# 1_P1.net
KiCad netlist of a schematic drawn in Altium Designer
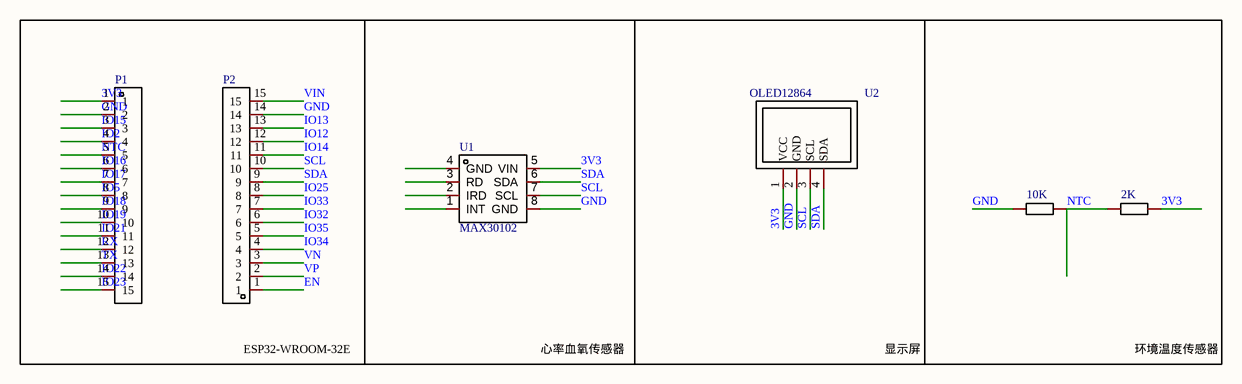
[diagram p0: 1_P1.schdoc]

(export (version "E")
  (design (tool "Eeschema 10.0.6"))
  (components
    (comp (ref "2K") (value "10K插件电阻") (libsource (lib "altium-import") (part "root_0_10K插件电阻_")))
    (comp (ref "10K")
      (value "10K")
      (fields (field (name "MANUFACTURER") "UniOhm") (field (name "MANUFACTURER PART") "0603WAF1002T5E"))
      (libsource (lib "altium-import") (part "root_0_10K_"))
    )
    (comp (ref "P1") (value "排针15pin") (libsource (lib "altium-import") (part "root_0_排针15pin_")))
    (comp (ref "P2") (value "排针15pin") (libsource (lib "altium-import") (part "root_2_排针15pin_")))
    (comp (ref "U1") (value "MAX30102") (libsource (lib "altium-import") (part "root_0_MAX30102_")))
    (comp (ref "U2") (value "OLED12864") (libsource (lib "altium-import") (part "root_0_OLED12864_")))
  )
  (nets
    (net (code "1") (name "/3V3") (class "Default")
      (node (ref "2K") (pin "2") (pinfunction "2_2") (pintype "passive"))
      (node (ref "P1") (pin "1") (pinfunction "1_1") (pintype "passive"))
      (node (ref "U1") (pin "5") (pinfunction "VIN_5") (pintype "passive"))
      (node (ref "U2") (pin "1") (pinfunction "VCC_1") (pintype "passive"))
    )
    (net (code "2") (name "/EN") (class "Default")
      (node (ref "P2") (pin "1") (pinfunction "1_1") (pintype "passive"))
    )
    (net (code "3") (name "/GND") (class "Default")
      (node (ref "10K") (pin "1") (pinfunction "1_1") (pintype "passive"))
      (node (ref "P1") (pin "2") (pinfunction "2_2") (pintype "passive"))
      (node (ref "P2") (pin "14") (pinfunction "14_14") (pintype "passive"))
      (node (ref "U1") (pin "8") (pinfunction "GND_8") (pintype "passive"))
      (node (ref "U2") (pin "2") (pinfunction "GND_2") (pintype "passive"))
    )
    (net (code "4") (name "/IO2") (class "Default")
      (node (ref "P1") (pin "4") (pinfunction "4_4") (pintype "passive"))
    )
    (net (code "5") (name "/IO5") (class "Default")
      (node (ref "P1") (pin "8") (pinfunction "8_8") (pintype "passive"))
    )
    (net (code "6") (name "/IO12") (class "Default")
      (node (ref "P2") (pin "12") (pinfunction "12_12") (pintype "passive"))
    )
    (net (code "7") (name "/IO13") (class "Default")
      (node (ref "P2") (pin "13") (pinfunction "13_13") (pintype "passive"))
    )
    (net (code "8") (name "/IO14") (class "Default")
      (node (ref "P2") (pin "11") (pinfunction "11_11") (pintype "passive"))
    )
    (net (code "9") (name "/IO15") (class "Default")
      (node (ref "P1") (pin "3") (pinfunction "3_3") (pintype "passive"))
    )
    (net (code "10") (name "/IO16") (class "Default")
      (node (ref "P1") (pin "6") (pinfunction "6_6") (pintype "passive"))
    )
    (net (code "11") (name "/IO17") (class "Default")
      (node (ref "P1") (pin "7") (pinfunction "7_7") (pintype "passive"))
    )
    (net (code "12") (name "/IO18") (class "Default")
      (node (ref "P1") (pin "9") (pinfunction "9_9") (pintype "passive"))
    )
    (net (code "13") (name "/IO19") (class "Default")
      (node (ref "P1") (pin "10") (pinfunction "10_10") (pintype "passive"))
    )
    (net (code "14") (name "/IO21") (class "Default")
      (node (ref "P1") (pin "11") (pinfunction "11_11") (pintype "passive"))
    )
    (net (code "15") (name "/IO22") (class "Default")
      (node (ref "P1") (pin "14") (pinfunction "14_14") (pintype "passive"))
    )
    (net (code "16") (name "/IO23") (class "Default")
      (node (ref "P1") (pin "15") (pinfunction "15_15") (pintype "passive"))
    )
    (net (code "17") (name "/IO25") (class "Default")
      (node (ref "P2") (pin "8") (pinfunction "8_8") (pintype "passive"))
    )
    (net (code "18") (name "/IO32") (class "Default")
      (node (ref "P2") (pin "6") (pinfunction "6_6") (pintype "passive"))
    )
    (net (code "19") (name "/IO33") (class "Default")
      (node (ref "P2") (pin "7") (pinfunction "7_7") (pintype "passive"))
    )
    (net (code "20") (name "/IO34") (class "Default")
      (node (ref "P2") (pin "4") (pinfunction "4_4") (pintype "passive"))
    )
    (net (code "21") (name "/IO35") (class "Default")
      (node (ref "P2") (pin "5") (pinfunction "5_5") (pintype "passive"))
    )
    (net (code "22") (name "/NTC") (class "Default")
      (node (ref "10K") (pin "2") (pinfunction "2_2") (pintype "passive"))
      (node (ref "2K") (pin "1") (pinfunction "1_1") (pintype "passive"))
      (node (ref "P1") (pin "5") (pinfunction "5_5") (pintype "passive"))
    )
    (net (code "23") (name "/RX") (class "Default")
      (node (ref "P1") (pin "12") (pinfunction "12_12") (pintype "passive"))
    )
    (net (code "24") (name "/SCL") (class "Default")
      (node (ref "P2") (pin "10") (pinfunction "10_10") (pintype "passive"))
      (node (ref "U1") (pin "7") (pinfunction "SCL_7") (pintype "passive"))
      (node (ref "U2") (pin "3") (pinfunction "SCL_3") (pintype "passive"))
    )
    (net (code "25") (name "/SDA") (class "Default")
      (node (ref "P2") (pin "9") (pinfunction "9_9") (pintype "passive"))
      (node (ref "U1") (pin "6") (pinfunction "SDA_6") (pintype "passive"))
      (node (ref "U2") (pin "4") (pinfunction "SDA_4") (pintype "passive"))
    )
    (net (code "26") (name "/TX") (class "Default")
      (node (ref "P1") (pin "13") (pinfunction "13_13") (pintype "passive"))
    )
    (net (code "27") (name "/VIN") (class "Default")
      (node (ref "P2") (pin "15") (pinfunction "15_15") (pintype "passive"))
    )
    (net (code "28") (name "/VN") (class "Default")
      (node (ref "P2") (pin "3") (pinfunction "3_3") (pintype "passive"))
    )
    (net (code "29") (name "/VP") (class "Default")
      (node (ref "P2") (pin "2") (pinfunction "2_2") (pintype "passive"))
    )
    (net (code "30") (name "unconnected-(U1-GND-Pad4)") (class "Default")
      (node (ref "U1") (pin "4") (pinfunction "GND_4") (pintype "passive"))
    )
    (net (code "31") (name "unconnected-(U1-INT-Pad1)") (class "Default")
      (node (ref "U1") (pin "1") (pinfunction "INT_1") (pintype "passive"))
    )
    (net (code "32") (name "unconnected-(U1-IRD-Pad2)") (class "Default")
      (node (ref "U1") (pin "2") (pinfunction "IRD_2") (pintype "passive"))
    )
    (net (code "33") (name "unconnected-(U1-RD-Pad3)") (class "Default")
      (node (ref "U1") (pin "3") (pinfunction "RD_3") (pintype "passive"))
    )
  )
)
